# prog_addapter_rev1_1.net
KiCad netlist of a schematic drawn in EAGLE
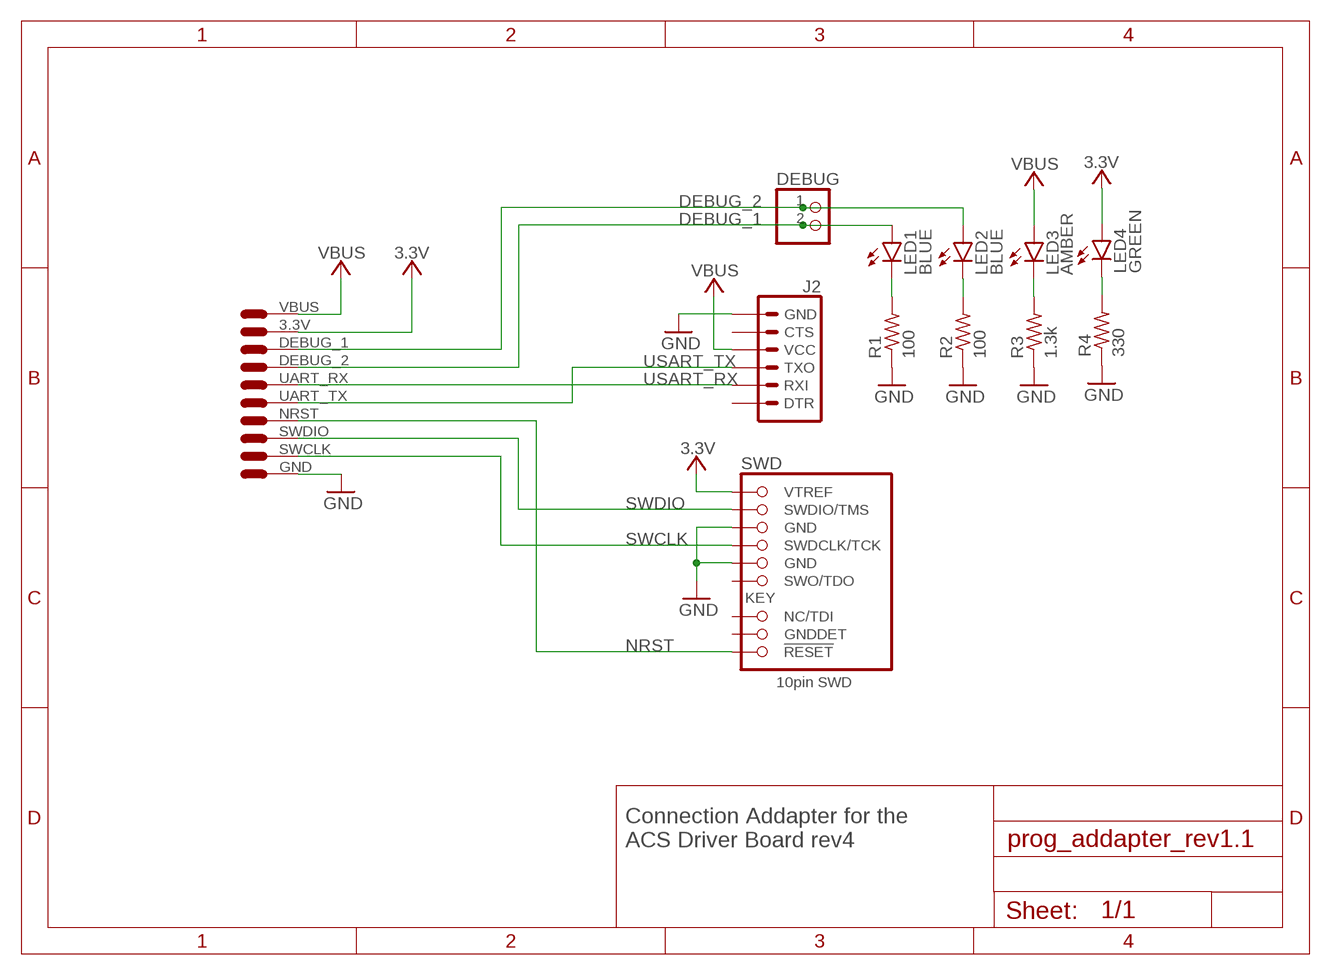
[diagram p0: schematic, sheet 1]

(export (version "E")
  (design (tool "Eeschema 10.0.6"))
  (components
    (comp (ref "DEBUG")
      (value "PINHD-1X2")
      (footprint "eagle-import:1X02")
      (libsource (lib "eagle-import") (part "PINHD-1X2"))
    )
    (comp (ref "J2")
      (value "6_PIN_SERIAL_TARGETSILK")
      (footprint "eagle-import:6_PIN_SERIAL_TARGET_SIDE_W_SILK")
      (libsource (lib "eagle-import") (part "6_PIN_SERIAL_TARGETSILK"))
    )
    (comp (ref "LED1")
      (value "BLUE")
      (footprint "eagle-import:CHIPLED_0603")
      (libsource (lib "eagle-import") (part "LEDCHIPLED_0603"))
    )
    (comp (ref "LED2")
      (value "BLUE")
      (footprint "eagle-import:CHIPLED_0603")
      (libsource (lib "eagle-import") (part "LEDCHIPLED_0603"))
    )
    (comp (ref "LED3")
      (value "AMBER")
      (footprint "eagle-import:CHIPLED_0603")
      (libsource (lib "eagle-import") (part "LEDCHIPLED_0603"))
    )
    (comp (ref "LED4")
      (value "GREEN")
      (footprint "eagle-import:CHIPLED_0603")
      (libsource (lib "eagle-import") (part "LEDCHIPLED_0603"))
    )
    (comp (ref "R1")
      (value "100")
      (footprint "eagle-import:.0402-B-NOSILK")
      (libsource (lib "eagle-import") (part "R-US_0402-B-NOSILK"))
    )
    (comp (ref "R2")
      (value "100")
      (footprint "eagle-import:.0402-B-NOSILK")
      (libsource (lib "eagle-import") (part "R-US_0402-B-NOSILK"))
    )
    (comp (ref "R3")
      (value "1.3k")
      (footprint "eagle-import:.0402-B-NOSILK")
      (libsource (lib "eagle-import") (part "R-US_0402-B-NOSILK"))
    )
    (comp (ref "R4")
      (value "330")
      (footprint "eagle-import:.0402-B-NOSILK")
      (libsource (lib "eagle-import") (part "R-US_0402-B-NOSILK"))
    )
    (comp (ref "SWD")
      (value "1.27MM-SWD-CONNECTOR")
      (footprint "eagle-import:1.27MM_2X5")
      (libsource (lib "eagle-import") (part "1.27MM-SWD-CONNECTOR"))
    )
    (comp (ref "U$1")
      (value "DEBUG_CON")
      (footprint "eagle-import:DEBUG_CON")
      (libsource (lib "eagle-import") (part "DEBUG_CON"))
    )
  )
  (nets
    (net (code "1") (name "/DEBUG_1") (class "Default")
      (node (ref "DEBUG") (pin "1") (pinfunction "1_1") (pintype "passive"))
      (node (ref "LED2") (pin "A") (pinfunction "A_A") (pintype "passive"))
      (node (ref "U$1") (pin "DEBUG_1") (pinfunction "3_DEBUG_1") (pintype "bidirectional"))
    )
    (net (code "2") (name "/DEBUG_2") (class "Default")
      (node (ref "DEBUG") (pin "2") (pinfunction "2_2") (pintype "passive"))
      (node (ref "LED1") (pin "A") (pinfunction "A_A") (pintype "passive"))
      (node (ref "U$1") (pin "DEBUG_2") (pinfunction "4_DEBUG_2") (pintype "bidirectional"))
    )
    (net (code "3") (name "/NRST") (class "Default")
      (node (ref "SWD") (pin "!RESET") (pinfunction "~{RESET}_!RESET") (pintype "passive"))
      (node (ref "U$1") (pin "NRST") (pinfunction "7_NRST") (pintype "bidirectional"))
    )
    (net (code "4") (name "/SWCLK") (class "Default")
      (node (ref "SWD") (pin "SWDCLK") (pinfunction "SWDCLK/TCK_SWDCLK") (pintype "passive"))
      (node (ref "U$1") (pin "SWCLK") (pinfunction "9_SWCLK") (pintype "bidirectional"))
    )
    (net (code "5") (name "/SWDIO") (class "Default")
      (node (ref "SWD") (pin "SWDIO") (pinfunction "SWDIO/TMS_SWDIO") (pintype "passive"))
      (node (ref "U$1") (pin "SWDIO") (pinfunction "8_SWDIO") (pintype "bidirectional"))
    )
    (net (code "6") (name "/USART_RX") (class "Default")
      (node (ref "J2") (pin "P$3") (pinfunction "RXI_P$3") (pintype "passive"))
      (node (ref "U$1") (pin "UART_RX") (pinfunction "5_UART_RX") (pintype "bidirectional"))
    )
    (net (code "7") (name "/USART_TX") (class "Default")
      (node (ref "J2") (pin "P$2") (pinfunction "TXO_P$2") (pintype "passive"))
      (node (ref "U$1") (pin "UART_TX") (pinfunction "6_UART_TX") (pintype "bidirectional"))
    )
    (net (code "8") (name "3.3V") (class "Default")
      (node (ref "LED4") (pin "A") (pinfunction "A_A") (pintype "passive"))
      (node (ref "SWD") (pin "VTREF") (pinfunction "VTREF_VTREF") (pintype "passive"))
      (node (ref "U$1") (pin "3.3V") (pinfunction "2_3.3V") (pintype "bidirectional"))
    )
    (net (code "9") (name "GND") (class "Default")
      (node (ref "J2") (pin "P$6") (pinfunction "GND_P$6") (pintype "passive"))
      (node (ref "R1") (pin "1") (pinfunction "1_1") (pintype "passive"))
      (node (ref "R2") (pin "1") (pinfunction "1_1") (pintype "passive"))
      (node (ref "R3") (pin "1") (pinfunction "1_1") (pintype "passive"))
      (node (ref "R4") (pin "1") (pinfunction "1_1") (pintype "passive"))
      (node (ref "SWD") (pin "GND") (pinfunction "GND_GND") (pintype "passive"))
      (node (ref "SWD") (pin "GND@2") (pinfunction "GND_GND@2") (pintype "passive"))
      (node (ref "U$1") (pin "GND") (pinfunction "10_GND") (pintype "bidirectional"))
    )
    (net (code "10") (name "Net-(LED1-PadC)") (class "Default")
      (node (ref "LED1") (pin "C") (pinfunction "C_C") (pintype "passive"))
      (node (ref "R1") (pin "2") (pinfunction "2_2") (pintype "passive"))
    )
    (net (code "11") (name "Net-(LED2-PadC)") (class "Default")
      (node (ref "LED2") (pin "C") (pinfunction "C_C") (pintype "passive"))
      (node (ref "R2") (pin "2") (pinfunction "2_2") (pintype "passive"))
    )
    (net (code "12") (name "Net-(LED3-PadC)") (class "Default")
      (node (ref "LED3") (pin "C") (pinfunction "C_C") (pintype "passive"))
      (node (ref "R3") (pin "2") (pinfunction "2_2") (pintype "passive"))
    )
    (net (code "13") (name "Net-(LED4-PadC)") (class "Default")
      (node (ref "LED4") (pin "C") (pinfunction "C_C") (pintype "passive"))
      (node (ref "R4") (pin "2") (pinfunction "2_2") (pintype "passive"))
    )
    (net (code "14") (name "VBUS") (class "Default")
      (node (ref "J2") (pin "P$4") (pinfunction "VCC_P$4") (pintype "passive"))
      (node (ref "LED3") (pin "A") (pinfunction "A_A") (pintype "passive"))
      (node (ref "U$1") (pin "VBUS") (pinfunction "1_VBUS") (pintype "bidirectional"))
    )
    (net (code "15") (name "unconnected-(J2-CTS-PadP$5)") (class "Default")
      (node (ref "J2") (pin "P$5") (pinfunction "CTS_P$5") (pintype "passive"))
    )
    (net (code "16") (name "unconnected-(J2-DTR-PadP$1)") (class "Default")
      (node (ref "J2") (pin "P$1") (pinfunction "DTR_P$1") (pintype "passive"))
    )
    (net (code "17") (name "unconnected-(SWD-NC{slash}TDI-PadNC)") (class "Default")
      (node (ref "SWD") (pin "NC") (pinfunction "NC/TDI_NC") (pintype "passive"))
    )
    (net (code "18") (name "unconnected-(SWD-PadGNDDET)") (class "Default")
      (node (ref "SWD") (pin "GNDDET") (pinfunction "GNDDET_GNDDET") (pintype "passive"))
    )
    (net (code "19") (name "unconnected-(SWD-SWO{slash}TDO-PadSWO)") (class "Default")
      (node (ref "SWD") (pin "SWO") (pinfunction "SWO/TDO_SWO") (pintype "passive"))
    )
  )
)
